# schemat.net
KiCad netlist of a schematic drawn in EAGLE
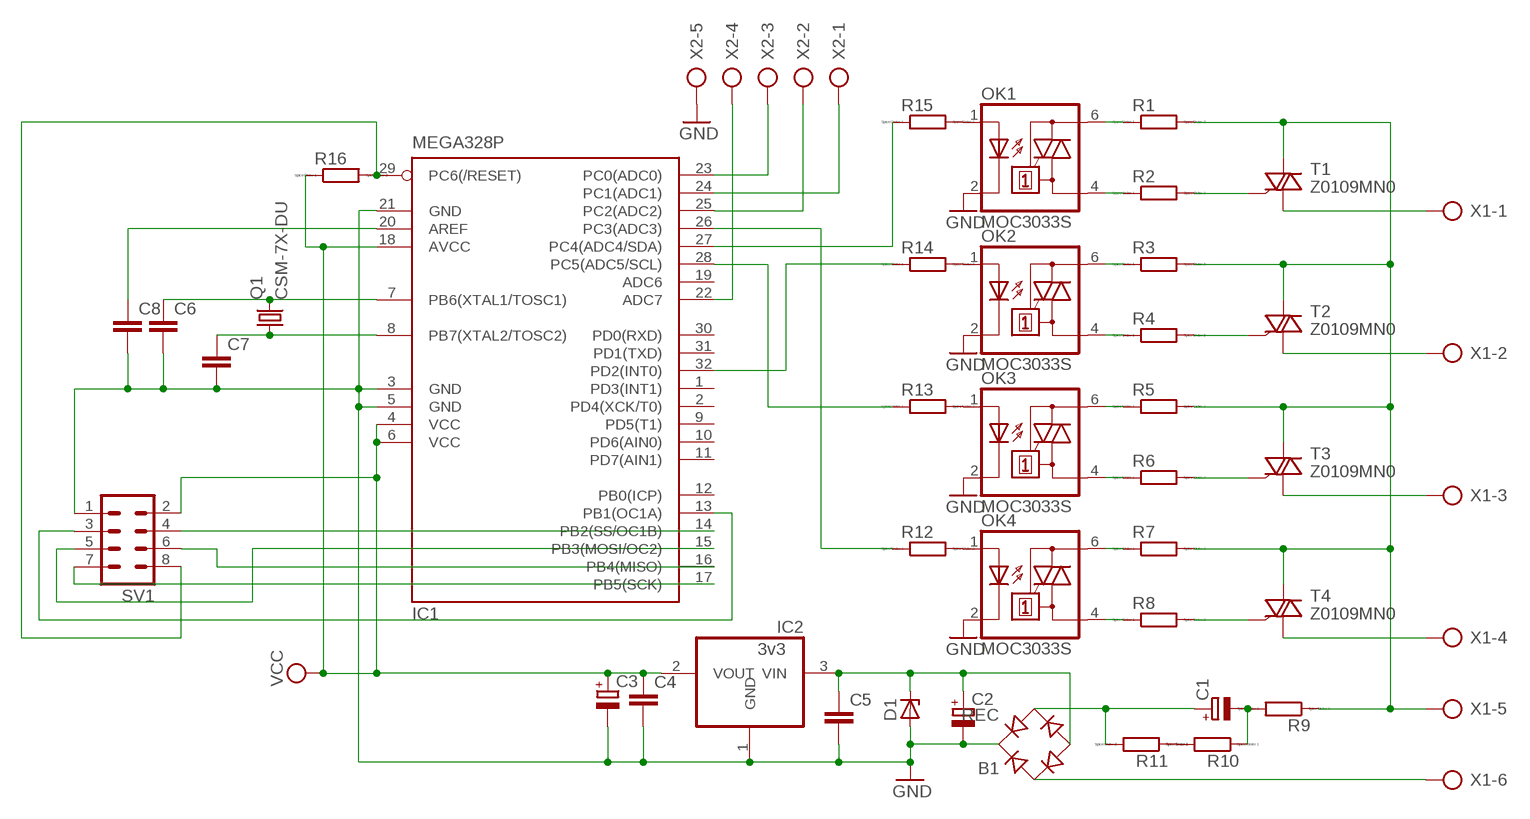
[diagram p0: schematic, sheet 1]

(export (version "E")
  (design (tool "Eeschema 10.0.6"))
  (components
    (comp (ref "B1")
      (value "REC")
      (footprint "eagle-import:B40S")
      (libsource (lib "eagle-import") (part "RECTIFIER-B40S"))
    )
    (comp (ref "C1")
      (value "CPOL-EU139CLL-2W")
      (footprint "eagle-import:139CLL-2W")
      (libsource (lib "eagle-import") (part "CPOL-EU139CLL-2W"))
    )
    (comp (ref "C2")
      (value "CPOL-EU140CLH-1010")
      (footprint "eagle-import:140CLH-1010")
      (libsource (lib "eagle-import") (part "CPOL-EU140CLH-1010"))
    )
    (comp (ref "C3")
      (value "CPOL-EU140CLH-1010")
      (footprint "eagle-import:140CLH-1010")
      (libsource (lib "eagle-import") (part "CPOL-EU140CLH-1010"))
    )
    (comp (ref "C4")
      (value "C-EUC1210")
      (footprint "eagle-import:C1210")
      (libsource (lib "eagle-import") (part "C-EUC1210"))
    )
    (comp (ref "C5")
      (value "C-EUC1210")
      (footprint "eagle-import:C1210")
      (libsource (lib "eagle-import") (part "C-EUC1210"))
    )
    (comp (ref "C6")
      (value "C-EUC1210")
      (footprint "eagle-import:C1210")
      (libsource (lib "eagle-import") (part "C-EUC1210"))
    )
    (comp (ref "C7")
      (value "C-EUC1210")
      (footprint "eagle-import:C1210")
      (libsource (lib "eagle-import") (part "C-EUC1210"))
    )
    (comp (ref "C8")
      (value "C-EUC1210")
      (footprint "eagle-import:C1210")
      (libsource (lib "eagle-import") (part "C-EUC1210"))
    )
    (comp (ref "D1")
      (value "ZENER-DIODESMB")
      (footprint "eagle-import:SMB")
      (libsource (lib "eagle-import") (part "ZENER-DIODESMB"))
    )
    (comp (ref "IC1")
      (value "MEGA328P")
      (footprint "eagle-import:TQFP32-08")
      (fields (field (name "MPN") "ATMEGA8-16AU"))
      (libsource (lib "eagle-import") (part "MEGA8-AI"))
    )
    (comp (ref "IC2")
      (value "3v3")
      (footprint "eagle-import:SOT223")
      (fields (field (name "MPN") "REG1117"))
      (libsource (lib "eagle-import") (part "REG1117"))
    )
    (comp (ref "OK1")
      (value "MOC3033S")
      (footprint "eagle-import:DIL6-SMD")
      (fields (field (name "MF") "FAIRCHILD SEMICONDUCTOR") (field (name "MPN") "MOC3033S-M"))
      (libsource (lib "eagle-import") (part "MOC30S33"))
    )
    (comp (ref "OK2")
      (value "MOC3033S")
      (footprint "eagle-import:DIL6-SMD")
      (fields (field (name "MF") "FAIRCHILD SEMICONDUCTOR") (field (name "MPN") "MOC3033S-M"))
      (libsource (lib "eagle-import") (part "MOC30S33"))
    )
    (comp (ref "OK3")
      (value "MOC3033S")
      (footprint "eagle-import:DIL6-SMD")
      (fields (field (name "MF") "FAIRCHILD SEMICONDUCTOR") (field (name "MPN") "MOC3033S-M"))
      (libsource (lib "eagle-import") (part "MOC30S33"))
    )
    (comp (ref "OK4")
      (value "MOC3033S")
      (footprint "eagle-import:DIL6-SMD")
      (fields (field (name "MF") "FAIRCHILD SEMICONDUCTOR") (field (name "MPN") "MOC3033S-M"))
      (libsource (lib "eagle-import") (part "MOC30S33"))
    )
    (comp (ref "Q1")
      (value "CSM-7X-DU")
      (footprint "eagle-import:CSM-7X-DU")
      (libsource (lib "eagle-import") (part "CSM-7X-DU"))
    )
    (comp (ref "R1")
      (value "RR1206")
      (footprint "eagle-import:R1206")
      (libsource (lib "eagle-import") (part "RR1206"))
    )
    (comp (ref "R2")
      (value "RR1206")
      (footprint "eagle-import:R1206")
      (libsource (lib "eagle-import") (part "RR1206"))
    )
    (comp (ref "R3")
      (value "RR1206")
      (footprint "eagle-import:R1206")
      (libsource (lib "eagle-import") (part "RR1206"))
    )
    (comp (ref "R4")
      (value "RR1206")
      (footprint "eagle-import:R1206")
      (libsource (lib "eagle-import") (part "RR1206"))
    )
    (comp (ref "R5")
      (value "RR1206")
      (footprint "eagle-import:R1206")
      (libsource (lib "eagle-import") (part "RR1206"))
    )
    (comp (ref "R6")
      (value "RR1206")
      (footprint "eagle-import:R1206")
      (libsource (lib "eagle-import") (part "RR1206"))
    )
    (comp (ref "R7")
      (value "RR1206")
      (footprint "eagle-import:R1206")
      (libsource (lib "eagle-import") (part "RR1206"))
    )
    (comp (ref "R8")
      (value "RR1206")
      (footprint "eagle-import:R1206")
      (libsource (lib "eagle-import") (part "RR1206"))
    )
    (comp (ref "R9")
      (value "RR2512")
      (footprint "eagle-import:R2512")
      (libsource (lib "eagle-import") (part "RR2512"))
    )
    (comp (ref "R10")
      (value "RR1210")
      (footprint "eagle-import:R1210")
      (libsource (lib "eagle-import") (part "RR1210"))
    )
    (comp (ref "R11")
      (value "RR1210")
      (footprint "eagle-import:R1210")
      (libsource (lib "eagle-import") (part "RR1210"))
    )
    (comp (ref "R12")
      (value "RR1206")
      (footprint "eagle-import:R1206")
      (libsource (lib "eagle-import") (part "RR1206"))
    )
    (comp (ref "R13")
      (value "RR1206")
      (footprint "eagle-import:R1206")
      (libsource (lib "eagle-import") (part "RR1206"))
    )
    (comp (ref "R14")
      (value "RR1206")
      (footprint "eagle-import:R1206")
      (libsource (lib "eagle-import") (part "RR1206"))
    )
    (comp (ref "R15")
      (value "RR1206")
      (footprint "eagle-import:R1206")
      (libsource (lib "eagle-import") (part "RR1206"))
    )
    (comp (ref "R16")
      (value "RR1206")
      (footprint "eagle-import:R1206")
      (libsource (lib "eagle-import") (part "RR1206"))
    )
    (comp (ref "SV1")
      (value "MA04-2")
      (footprint "eagle-import:MA04-2")
      (libsource (lib "eagle-import") (part "MA04-2"))
    )
    (comp (ref "T1")
      (value "Z0109MN0")
      (footprint "eagle-import:SOT223")
      (libsource (lib "eagle-import") (part "Z0109MN0"))
    )
    (comp (ref "T2")
      (value "Z0109MN0")
      (footprint "eagle-import:SOT223")
      (libsource (lib "eagle-import") (part "Z0109MN0"))
    )
    (comp (ref "T3")
      (value "Z0109MN0")
      (footprint "eagle-import:SOT223")
      (libsource (lib "eagle-import") (part "Z0109MN0"))
    )
    (comp (ref "T4")
      (value "Z0109MN0")
      (footprint "eagle-import:SOT223")
      (libsource (lib "eagle-import") (part "Z0109MN0"))
    )
    (comp (ref "X1")
      (value "AK500/6")
      (footprint "eagle-import:AK500_6")
      (libsource (lib "eagle-import") (part "AK500/6"))
    )
    (comp (ref "X2")
      (value "AK300/5")
      (footprint "eagle-import:AK300_5")
      (libsource (lib "eagle-import") (part "AK300/5"))
    )
  )
  (nets
    (net (code "1") (name "GND") (class "Default")
      (node (ref "B1") (pin "+") (pinfunction "+_+") (pintype "passive"))
      (node (ref "C2") (pin "-") (pinfunction "-_-") (pintype "passive"))
      (node (ref "C3") (pin "-") (pinfunction "-_-") (pintype "passive"))
      (node (ref "C4") (pin "2") (pinfunction "2_2") (pintype "passive"))
      (node (ref "C5") (pin "2") (pinfunction "2_2") (pintype "passive"))
      (node (ref "C6") (pin "2") (pinfunction "2_2") (pintype "passive"))
      (node (ref "C7") (pin "2") (pinfunction "2_2") (pintype "passive"))
      (node (ref "C8") (pin "2") (pinfunction "2_2") (pintype "passive"))
      (node (ref "D1") (pin "A") (pinfunction "A_A") (pintype "passive"))
      (node (ref "IC1") (pin "21") (pinfunction "GND_21") (pintype "power_in"))
      (node (ref "IC1") (pin "3") (pinfunction "GND_3") (pintype "power_in"))
      (node (ref "IC1") (pin "5") (pinfunction "GND_5") (pintype "power_in"))
      (node (ref "IC2") (pin "1") (pinfunction "GND_1") (pintype "power_in"))
      (node (ref "OK1") (pin "2") (pinfunction "C_2") (pintype "passive"))
      (node (ref "OK2") (pin "2") (pinfunction "C_2") (pintype "passive"))
      (node (ref "OK3") (pin "2") (pinfunction "C_2") (pintype "passive"))
      (node (ref "OK4") (pin "2") (pinfunction "C_2") (pintype "passive"))
      (node (ref "SV1") (pin "1") (pinfunction "1_1") (pintype "passive"))
      (node (ref "X2") (pin "5") (pinfunction "KL_5") (pintype "passive"))
    )
    (net (code "2") (name "Net-(B1-PadAC2)") (class "Default")
      (node (ref "B1") (pin "AC2") (pinfunction "AC2_AC2") (pintype "passive"))
      (node (ref "C1") (pin "+") (pinfunction "+_+") (pintype "passive"))
      (node (ref "R11") (pin "2") (pinfunction "2_2") (pintype "passive"))
    )
    (net (code "3") (name "Net-(C1-Pad-)") (class "Default")
      (node (ref "C1") (pin "-") (pinfunction "-_-") (pintype "passive"))
      (node (ref "R10") (pin "1") (pinfunction "1_1") (pintype "passive"))
      (node (ref "R9") (pin "2") (pinfunction "2_2") (pintype "passive"))
    )
    (net (code "4") (name "Net-(IC1-ADC7)") (class "Default")
      (node (ref "IC1") (pin "22") (pinfunction "ADC7_22") (pintype "bidirectional"))
      (node (ref "X2") (pin "4") (pinfunction "KL_4") (pintype "passive"))
    )
    (net (code "5") (name "Net-(IC1-AREF)") (class "Default")
      (node (ref "C8") (pin "1") (pinfunction "1_1") (pintype "passive"))
      (node (ref "IC1") (pin "20") (pinfunction "AREF_20") (pintype "passive"))
    )
    (net (code "6") (name "Net-(IC1-PB1(OC1A))") (class "Default")
      (node (ref "IC1") (pin "13") (pinfunction "PB1(OC1A)_13") (pintype "bidirectional"))
      (node (ref "SV1") (pin "3") (pinfunction "3_3") (pintype "passive"))
    )
    (net (code "7") (name "Net-(IC1-PB2(SS{slash}OC1B))") (class "Default")
      (node (ref "IC1") (pin "14") (pinfunction "PB2(SS/OC1B)_14") (pintype "bidirectional"))
      (node (ref "SV1") (pin "4") (pinfunction "4_4") (pintype "passive"))
    )
    (net (code "8") (name "Net-(IC1-PB3(MOSI{slash}OC2))") (class "Default")
      (node (ref "IC1") (pin "15") (pinfunction "PB3(MOSI/OC2)_15") (pintype "bidirectional"))
      (node (ref "SV1") (pin "5") (pinfunction "5_5") (pintype "passive"))
    )
    (net (code "9") (name "Net-(IC1-PB4(MISO))") (class "Default")
      (node (ref "IC1") (pin "16") (pinfunction "PB4(MISO)_16") (pintype "bidirectional"))
      (node (ref "SV1") (pin "6") (pinfunction "6_6") (pintype "passive"))
    )
    (net (code "10") (name "Net-(IC1-PB5(SCK))") (class "Default")
      (node (ref "IC1") (pin "17") (pinfunction "PB5(SCK)_17") (pintype "bidirectional"))
      (node (ref "SV1") (pin "7") (pinfunction "7_7") (pintype "passive"))
    )
    (net (code "11") (name "Net-(IC1-PB6(XTAL1{slash}TOSC1))") (class "Default")
      (node (ref "C6") (pin "1") (pinfunction "1_1") (pintype "passive"))
      (node (ref "IC1") (pin "7") (pinfunction "PB6(XTAL1/TOSC1)_7") (pintype "bidirectional"))
      (node (ref "Q1") (pin "2") (pinfunction "2_2") (pintype "passive"))
    )
    (net (code "12") (name "Net-(IC1-PB7(XTAL2{slash}TOSC2))") (class "Default")
      (node (ref "C7") (pin "1") (pinfunction "1_1") (pintype "passive"))
      (node (ref "IC1") (pin "8") (pinfunction "PB7(XTAL2/TOSC2)_8") (pintype "bidirectional"))
      (node (ref "Q1") (pin "1") (pinfunction "1_1") (pintype "passive"))
    )
    (net (code "13") (name "Net-(IC1-PC0(ADC0))") (class "Default")
      (node (ref "IC1") (pin "23") (pinfunction "PC0(ADC0)_23") (pintype "bidirectional"))
      (node (ref "X2") (pin "3") (pinfunction "KL_3") (pintype "passive"))
    )
    (net (code "14") (name "Net-(IC1-PC1(ADC1))") (class "Default")
      (node (ref "IC1") (pin "24") (pinfunction "PC1(ADC1)_24") (pintype "bidirectional"))
      (node (ref "X2") (pin "1") (pinfunction "KL_1") (pintype "passive"))
    )
    (net (code "15") (name "Net-(IC1-PC2(ADC2))") (class "Default")
      (node (ref "IC1") (pin "25") (pinfunction "PC2(ADC2)_25") (pintype "bidirectional"))
      (node (ref "X2") (pin "2") (pinfunction "KL_2") (pintype "passive"))
    )
    (net (code "16") (name "Net-(IC1-PC3(ADC3))") (class "Default")
      (node (ref "IC1") (pin "26") (pinfunction "PC3(ADC3)_26") (pintype "bidirectional"))
      (node (ref "R12") (pin "1") (pinfunction "1_1") (pintype "passive"))
    )
    (net (code "17") (name "Net-(IC1-PC4(ADC4{slash}SDA))") (class "Default")
      (node (ref "IC1") (pin "27") (pinfunction "PC4(ADC4/SDA)_27") (pintype "bidirectional"))
      (node (ref "R15") (pin "1") (pinfunction "1_1") (pintype "passive"))
    )
    (net (code "18") (name "Net-(IC1-PC5(ADC5{slash}SCL))") (class "Default")
      (node (ref "IC1") (pin "28") (pinfunction "PC5(ADC5/SCL)_28") (pintype "bidirectional"))
      (node (ref "R13") (pin "1") (pinfunction "1_1") (pintype "passive"))
    )
    (net (code "19") (name "Net-(IC1-PC6({slash}RESET))") (class "Default")
      (node (ref "IC1") (pin "29") (pinfunction "PC6(/RESET)_29") (pintype "bidirectional"))
      (node (ref "R16") (pin "2") (pinfunction "2_2") (pintype "passive"))
      (node (ref "SV1") (pin "8") (pinfunction "8_8") (pintype "passive"))
    )
    (net (code "20") (name "Net-(IC1-PD2(INT0))") (class "Default")
      (node (ref "IC1") (pin "32") (pinfunction "PD2(INT0)_32") (pintype "bidirectional"))
      (node (ref "R14") (pin "1") (pinfunction "1_1") (pintype "passive"))
    )
    (net (code "21") (name "Net-(IC2-VIN)") (class "Default")
      (node (ref "B1") (pin "-") (pinfunction "-_-") (pintype "passive"))
      (node (ref "C2") (pin "+") (pinfunction "+_+") (pintype "passive"))
      (node (ref "C5") (pin "1") (pinfunction "1_1") (pintype "passive"))
      (node (ref "D1") (pin "C") (pinfunction "C_C") (pintype "passive"))
      (node (ref "IC2") (pin "3") (pinfunction "VIN_3") (pintype "input"))
    )
    (net (code "22") (name "Net-(OK1-A)") (class "Default")
      (node (ref "OK1") (pin "1") (pinfunction "A_1") (pintype "passive"))
      (node (ref "R15") (pin "2") (pinfunction "2_2") (pintype "passive"))
    )
    (net (code "23") (name "Net-(OK1-A1)") (class "Default")
      (node (ref "OK1") (pin "4") (pinfunction "A1_4") (pintype "passive"))
      (node (ref "R2") (pin "1") (pinfunction "1_1") (pintype "passive"))
    )
    (net (code "24") (name "Net-(OK1-A2)") (class "Default")
      (node (ref "OK1") (pin "6") (pinfunction "A2_6") (pintype "passive"))
      (node (ref "R1") (pin "1") (pinfunction "1_1") (pintype "passive"))
    )
    (net (code "25") (name "Net-(OK2-A)") (class "Default")
      (node (ref "OK2") (pin "1") (pinfunction "A_1") (pintype "passive"))
      (node (ref "R14") (pin "2") (pinfunction "2_2") (pintype "passive"))
    )
    (net (code "26") (name "Net-(OK2-A1)") (class "Default")
      (node (ref "OK2") (pin "4") (pinfunction "A1_4") (pintype "passive"))
      (node (ref "R4") (pin "1") (pinfunction "1_1") (pintype "passive"))
    )
    (net (code "27") (name "Net-(OK2-A2)") (class "Default")
      (node (ref "OK2") (pin "6") (pinfunction "A2_6") (pintype "passive"))
      (node (ref "R3") (pin "1") (pinfunction "1_1") (pintype "passive"))
    )
    (net (code "28") (name "Net-(OK3-A)") (class "Default")
      (node (ref "OK3") (pin "1") (pinfunction "A_1") (pintype "passive"))
      (node (ref "R13") (pin "2") (pinfunction "2_2") (pintype "passive"))
    )
    (net (code "29") (name "Net-(OK3-A1)") (class "Default")
      (node (ref "OK3") (pin "4") (pinfunction "A1_4") (pintype "passive"))
      (node (ref "R6") (pin "1") (pinfunction "1_1") (pintype "passive"))
    )
    (net (code "30") (name "Net-(OK3-A2)") (class "Default")
      (node (ref "OK3") (pin "6") (pinfunction "A2_6") (pintype "passive"))
      (node (ref "R5") (pin "1") (pinfunction "1_1") (pintype "passive"))
    )
    (net (code "31") (name "Net-(OK4-A)") (class "Default")
      (node (ref "OK4") (pin "1") (pinfunction "A_1") (pintype "passive"))
      (node (ref "R12") (pin "2") (pinfunction "2_2") (pintype "passive"))
    )
    (net (code "32") (name "Net-(OK4-A1)") (class "Default")
      (node (ref "OK4") (pin "4") (pinfunction "A1_4") (pintype "passive"))
      (node (ref "R8") (pin "1") (pinfunction "1_1") (pintype "passive"))
    )
    (net (code "33") (name "Net-(OK4-A2)") (class "Default")
      (node (ref "OK4") (pin "6") (pinfunction "A2_6") (pintype "passive"))
      (node (ref "R7") (pin "1") (pinfunction "1_1") (pintype "passive"))
    )
    (net (code "34") (name "Net-(R10-Pad2)") (class "Default")
      (node (ref "R10") (pin "2") (pinfunction "2_2") (pintype "passive"))
      (node (ref "R11") (pin "1") (pinfunction "1_1") (pintype "passive"))
    )
    (net (code "35") (name "Net-(T1-G)") (class "Default")
      (node (ref "R2") (pin "2") (pinfunction "2_2") (pintype "passive"))
      (node (ref "T1") (pin "3") (pinfunction "G_3") (pintype "passive"))
    )
    (net (code "36") (name "Net-(T1-LD)") (class "Default")
      (node (ref "R1") (pin "2") (pinfunction "2_2") (pintype "passive"))
      (node (ref "R3") (pin "2") (pinfunction "2_2") (pintype "passive"))
      (node (ref "R5") (pin "2") (pinfunction "2_2") (pintype "passive"))
      (node (ref "R7") (pin "2") (pinfunction "2_2") (pintype "passive"))
      (node (ref "R9") (pin "1") (pinfunction "1_1") (pintype "passive"))
      (node (ref "T1") (pin "1") (pinfunction "LD_1") (pintype "passive"))
      (node (ref "T2") (pin "1") (pinfunction "LD_1") (pintype "passive"))
      (node (ref "T3") (pin "1") (pinfunction "LD_1") (pintype "passive"))
      (node (ref "T4") (pin "1") (pinfunction "LD_1") (pintype "passive"))
      (node (ref "X1") (pin "5") (pinfunction "KL_5") (pintype "passive"))
    )
    (net (code "37") (name "Net-(T2-G)") (class "Default")
      (node (ref "R4") (pin "2") (pinfunction "2_2") (pintype "passive"))
      (node (ref "T2") (pin "3") (pinfunction "G_3") (pintype "passive"))
    )
    (net (code "38") (name "Net-(T3-G)") (class "Default")
      (node (ref "R6") (pin "2") (pinfunction "2_2") (pintype "passive"))
      (node (ref "T3") (pin "3") (pinfunction "G_3") (pintype "passive"))
    )
    (net (code "39") (name "Net-(T4-G)") (class "Default")
      (node (ref "R8") (pin "2") (pinfunction "2_2") (pintype "passive"))
      (node (ref "T4") (pin "3") (pinfunction "G_3") (pintype "passive"))
    )
    (net (code "40") (name "Net-(X1A-KL)") (class "Default")
      (node (ref "T1") (pin "2") (pinfunction "CM_2") (pintype "passive"))
      (node (ref "T1") (pin "4") (pinfunction "CM_4") (pintype "passive"))
      (node (ref "X1") (pin "1") (pinfunction "KL_1") (pintype "passive"))
    )
    (net (code "41") (name "Net-(X1B-KL)") (class "Default")
      (node (ref "T2") (pin "2") (pinfunction "CM_2") (pintype "passive"))
      (node (ref "T2") (pin "4") (pinfunction "CM_4") (pintype "passive"))
      (node (ref "X1") (pin "2") (pinfunction "KL_2") (pintype "passive"))
    )
    (net (code "42") (name "Net-(X1C-KL)") (class "Default")
      (node (ref "T3") (pin "2") (pinfunction "CM_2") (pintype "passive"))
      (node (ref "T3") (pin "4") (pinfunction "CM_4") (pintype "passive"))
      (node (ref "X1") (pin "3") (pinfunction "KL_3") (pintype "passive"))
    )
    (net (code "43") (name "Net-(X1D-KL)") (class "Default")
      (node (ref "T4") (pin "2") (pinfunction "CM_2") (pintype "passive"))
      (node (ref "T4") (pin "4") (pinfunction "CM_4") (pintype "passive"))
      (node (ref "X1") (pin "4") (pinfunction "KL_4") (pintype "passive"))
    )
    (net (code "44") (name "Net-(X1F-KL)") (class "Default")
      (node (ref "B1") (pin "AC1") (pinfunction "AC1_AC1") (pintype "passive"))
      (node (ref "X1") (pin "6") (pinfunction "KL_6") (pintype "passive"))
    )
    (net (code "45") (name "VCC") (class "Default")
      (node (ref "C3") (pin "+") (pinfunction "+_+") (pintype "passive"))
      (node (ref "C4") (pin "1") (pinfunction "1_1") (pintype "passive"))
      (node (ref "IC1") (pin "18") (pinfunction "AVCC_18") (pintype "power_in"))
      (node (ref "IC1") (pin "4") (pinfunction "VCC_4") (pintype "power_in"))
      (node (ref "IC1") (pin "6") (pinfunction "VCC_6") (pintype "power_in"))
      (node (ref "IC2") (pin "2") (pinfunction "VOUT_2") (pintype "output"))
      (node (ref "R16") (pin "1") (pinfunction "1_1") (pintype "passive"))
      (node (ref "SV1") (pin "2") (pinfunction "2_2") (pintype "passive"))
    )
    (net (code "46") (name "unconnected-(IC1-ADC6-Pad19)") (class "Default")
      (node (ref "IC1") (pin "19") (pinfunction "ADC6_19") (pintype "bidirectional"))
    )
    (net (code "47") (name "unconnected-(IC1-PB0(ICP)-Pad12)") (class "Default")
      (node (ref "IC1") (pin "12") (pinfunction "PB0(ICP)_12") (pintype "bidirectional"))
    )
    (net (code "48") (name "unconnected-(IC1-PD0(RXD)-Pad30)") (class "Default")
      (node (ref "IC1") (pin "30") (pinfunction "PD0(RXD)_30") (pintype "bidirectional"))
    )
    (net (code "49") (name "unconnected-(IC1-PD1(TXD)-Pad31)") (class "Default")
      (node (ref "IC1") (pin "31") (pinfunction "PD1(TXD)_31") (pintype "bidirectional"))
    )
    (net (code "50") (name "unconnected-(IC1-PD3(INT1)-Pad1)") (class "Default")
      (node (ref "IC1") (pin "1") (pinfunction "PD3(INT1)_1") (pintype "bidirectional"))
    )
    (net (code "51") (name "unconnected-(IC1-PD4(XCK{slash}T0)-Pad2)") (class "Default")
      (node (ref "IC1") (pin "2") (pinfunction "PD4(XCK/T0)_2") (pintype "bidirectional"))
    )
    (net (code "52") (name "unconnected-(IC1-PD5(T1)-Pad9)") (class "Default")
      (node (ref "IC1") (pin "9") (pinfunction "PD5(T1)_9") (pintype "bidirectional"))
    )
    (net (code "53") (name "unconnected-(IC1-PD6(AIN0)-Pad10)") (class "Default")
      (node (ref "IC1") (pin "10") (pinfunction "PD6(AIN0)_10") (pintype "bidirectional"))
    )
    (net (code "54") (name "unconnected-(IC1-PD7(AIN1)-Pad11)") (class "Default")
      (node (ref "IC1") (pin "11") (pinfunction "PD7(AIN1)_11") (pintype "bidirectional"))
    )
  )
)
